# redbear.net
KiCad netlist of a schematic drawn in EAGLE
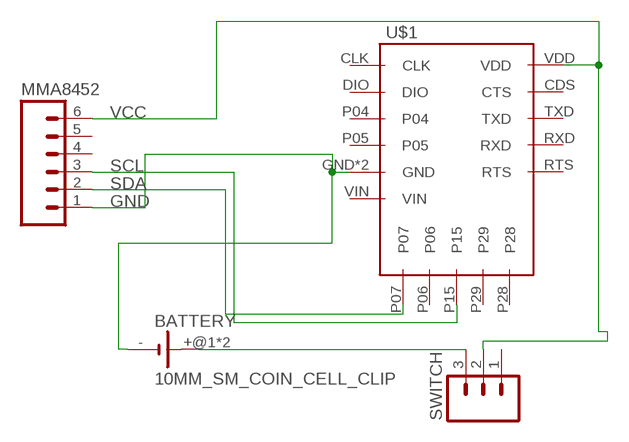
[diagram p0: schematic, sheet 1]

(export (version "E")
  (design (tool "Eeschema 10.0.6"))
  (components
    (comp (ref "BATTERY")
      (value "10MM_SM_COIN_CELL_CLIP")
      (footprint "eagle-import:10MM_SM_COIN_CELL_CLIP")
      (libsource (lib "eagle-import") (part "10MM_SM_COIN_CELL_CLIP"))
    )
    (comp (ref "MMA8452")
      (value "M06NO_SILK_FEMALE_PTH")
      (footprint "eagle-import:1X06_NO_SILK")
      (libsource (lib "eagle-import") (part "M06NO_SILK_FEMALE_PTH"))
    )
    (comp (ref "SWITCH")
      (value "M03PTH")
      (footprint "eagle-import:1X03")
      (libsource (lib "eagle-import") (part "M03PTH"))
    )
    (comp (ref "U$1")
      (value "REDBEAR_NANOBREAKOUT1")
      (footprint "eagle-import:BREAKOUT")
      (libsource (lib "eagle-import") (part "REDBEAR_NANOBREAKOUT1"))
    )
  )
  (nets
    (net (code "1") (name "/GND") (class "Default")
      (node (ref "BATTERY") (pin "-") (pinfunction "-_-") (pintype "passive"))
      (node (ref "MMA8452") (pin "1") (pinfunction "1_1") (pintype "passive"))
      (node (ref "U$1") (pin "GND") (pinfunction "GND_GND") (pintype "bidirectional"))
      (node (ref "U$1") (pin "GND1") (pinfunction "GND_GND1") (pintype "bidirectional"))
    )
    (net (code "2") (name "/SCL") (class "Default")
      (node (ref "MMA8452") (pin "3") (pinfunction "3_3") (pintype "passive"))
      (node (ref "U$1") (pin "P15") (pinfunction "P15_P15") (pintype "bidirectional"))
    )
    (net (code "3") (name "/SDA") (class "Default")
      (node (ref "MMA8452") (pin "2") (pinfunction "2_2") (pintype "passive"))
      (node (ref "U$1") (pin "P07") (pinfunction "P07_P07") (pintype "bidirectional"))
    )
    (net (code "4") (name "/VCC") (class "Default")
      (node (ref "MMA8452") (pin "6") (pinfunction "6_6") (pintype "passive"))
      (node (ref "SWITCH") (pin "2") (pinfunction "2_2") (pintype "passive"))
      (node (ref "U$1") (pin "VDD") (pinfunction "VDD_VDD") (pintype "bidirectional"))
    )
    (net (code "5") (name "Net-(BATTERY-+-Pad+@1)") (class "Default")
      (node (ref "BATTERY") (pin "+@1") (pinfunction "+_+@1") (pintype "passive"))
      (node (ref "BATTERY") (pin "+@2") (pinfunction "+_+@2") (pintype "passive"))
      (node (ref "SWITCH") (pin "3") (pinfunction "3_3") (pintype "passive"))
    )
    (net (code "6") (name "unconnected-(MMA8452-Pad4)") (class "Default")
      (node (ref "MMA8452") (pin "4") (pinfunction "4_4") (pintype "passive"))
    )
    (net (code "7") (name "unconnected-(MMA8452-Pad5)") (class "Default")
      (node (ref "MMA8452") (pin "5") (pinfunction "5_5") (pintype "passive"))
    )
    (net (code "8") (name "unconnected-(SWITCH-Pad1)") (class "Default")
      (node (ref "SWITCH") (pin "1") (pinfunction "1_1") (pintype "passive"))
    )
    (net (code "9") (name "unconnected-(U$1-CTS-PadCDS)") (class "Default")
      (node (ref "U$1") (pin "CDS") (pinfunction "CTS_CDS") (pintype "bidirectional"))
    )
    (net (code "10") (name "unconnected-(U$1-PadCLK)") (class "Default")
      (node (ref "U$1") (pin "CLK") (pinfunction "CLK_CLK") (pintype "bidirectional"))
    )
    (net (code "11") (name "unconnected-(U$1-PadDIO)") (class "Default")
      (node (ref "U$1") (pin "DIO") (pinfunction "DIO_DIO") (pintype "bidirectional"))
    )
    (net (code "12") (name "unconnected-(U$1-PadP04)") (class "Default")
      (node (ref "U$1") (pin "P04") (pinfunction "P04_P04") (pintype "bidirectional"))
    )
    (net (code "13") (name "unconnected-(U$1-PadP05)") (class "Default")
      (node (ref "U$1") (pin "P05") (pinfunction "P05_P05") (pintype "bidirectional"))
    )
    (net (code "14") (name "unconnected-(U$1-PadP06)") (class "Default")
      (node (ref "U$1") (pin "P06") (pinfunction "P06_P06") (pintype "bidirectional"))
    )
    (net (code "15") (name "unconnected-(U$1-PadP28)") (class "Default")
      (node (ref "U$1") (pin "P28") (pinfunction "P28_P28") (pintype "bidirectional"))
    )
    (net (code "16") (name "unconnected-(U$1-PadP29)") (class "Default")
      (node (ref "U$1") (pin "P29") (pinfunction "P29_P29") (pintype "bidirectional"))
    )
    (net (code "17") (name "unconnected-(U$1-PadRTS)") (class "Default")
      (node (ref "U$1") (pin "RTS") (pinfunction "RTS_RTS") (pintype "bidirectional"))
    )
    (net (code "18") (name "unconnected-(U$1-PadRXD)") (class "Default")
      (node (ref "U$1") (pin "RXD") (pinfunction "RXD_RXD") (pintype "bidirectional"))
    )
    (net (code "19") (name "unconnected-(U$1-PadTXD)") (class "Default")
      (node (ref "U$1") (pin "TXD") (pinfunction "TXD_TXD") (pintype "bidirectional"))
    )
    (net (code "20") (name "unconnected-(U$1-PadVIN)") (class "Default")
      (node (ref "U$1") (pin "VIN") (pinfunction "VIN_VIN") (pintype "bidirectional"))
    )
  )
)
